# Pure_VCF.net
KiCad netlist of a schematic drawn in EAGLE
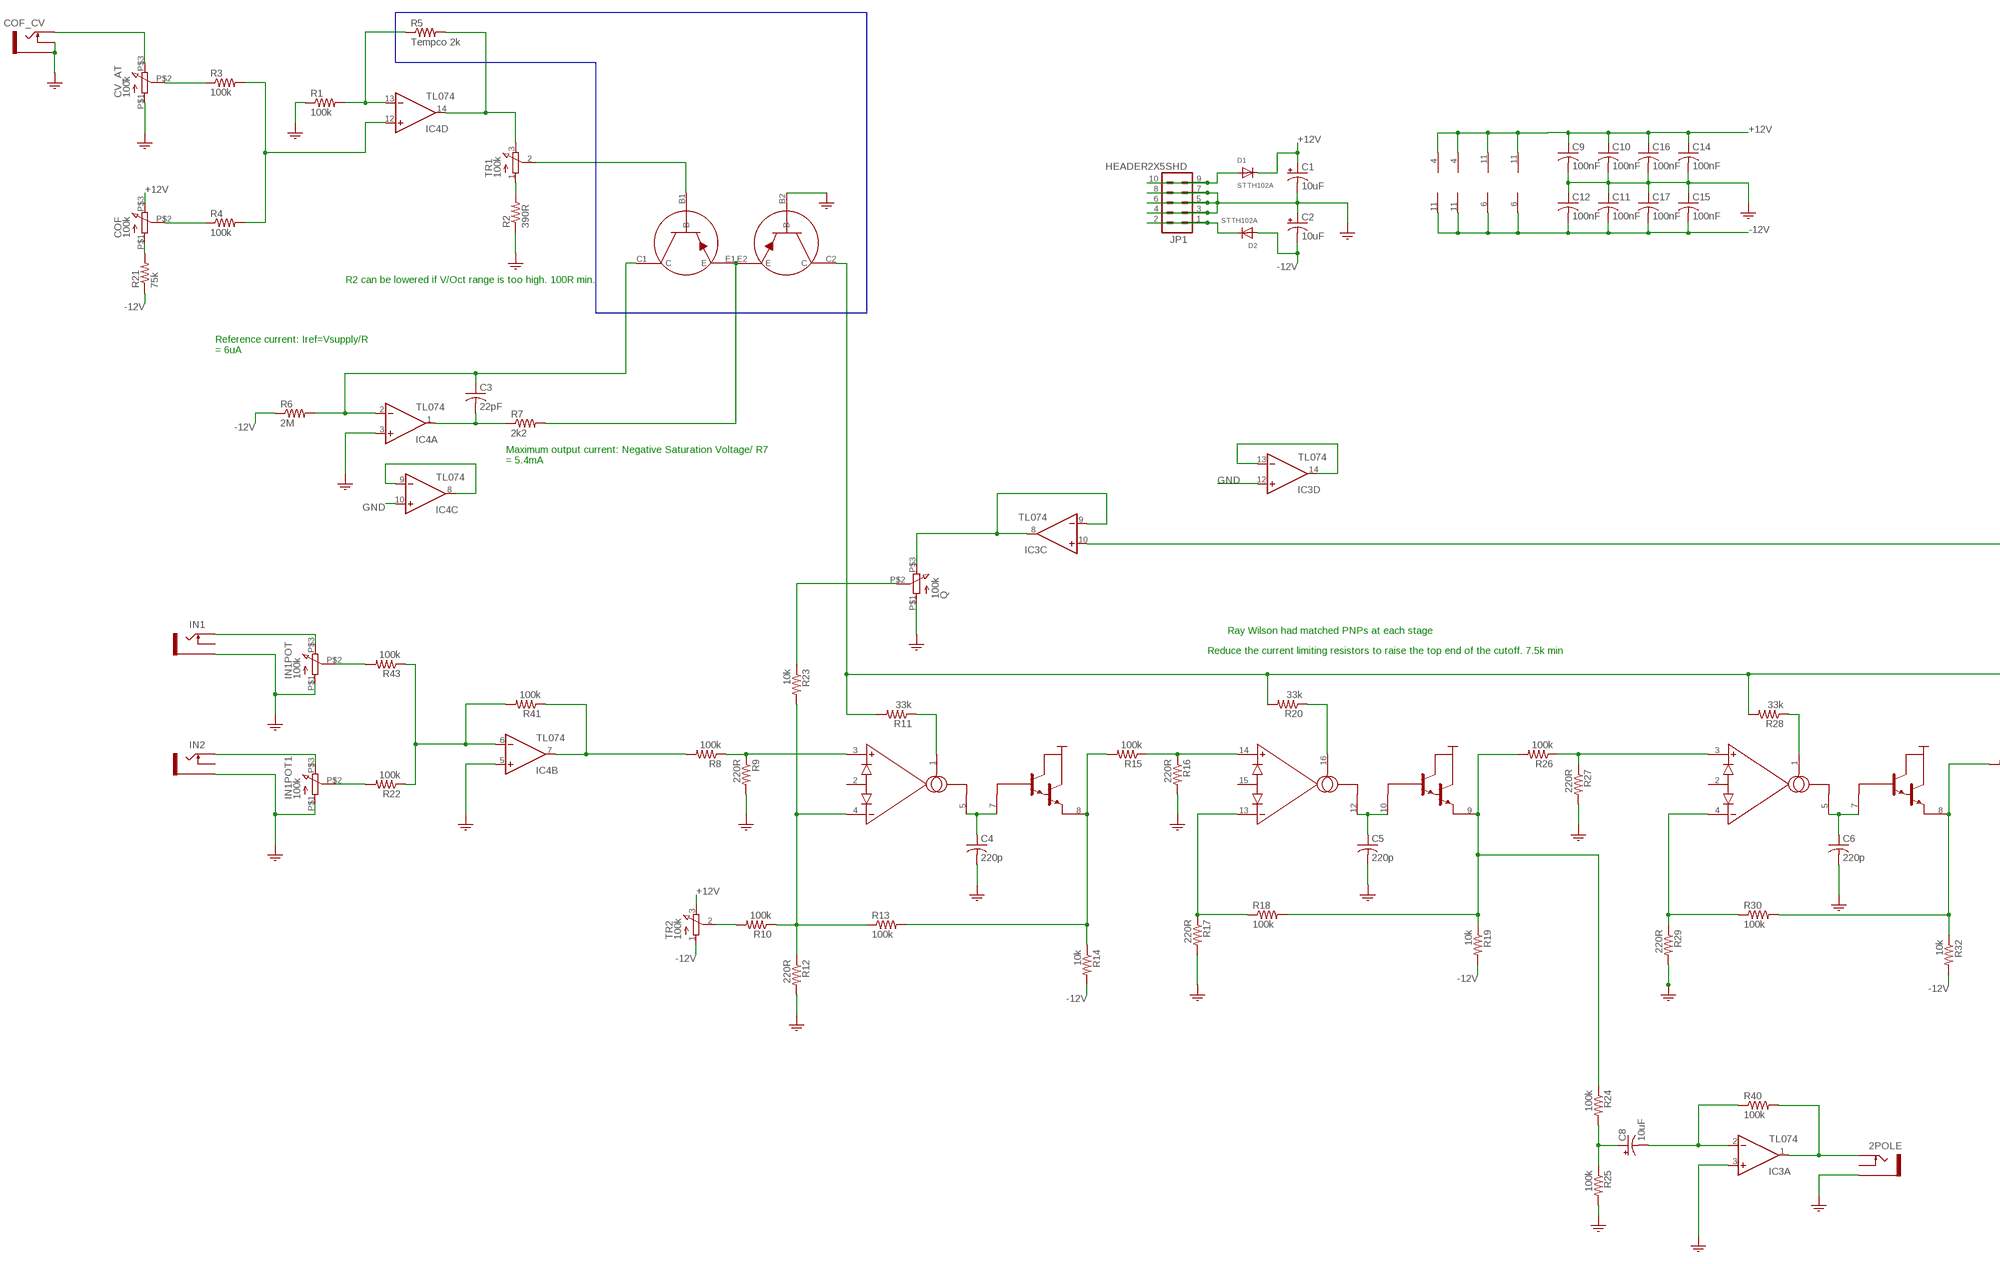
[diagram p0: schematic, sheet 1, part 1 of 2]
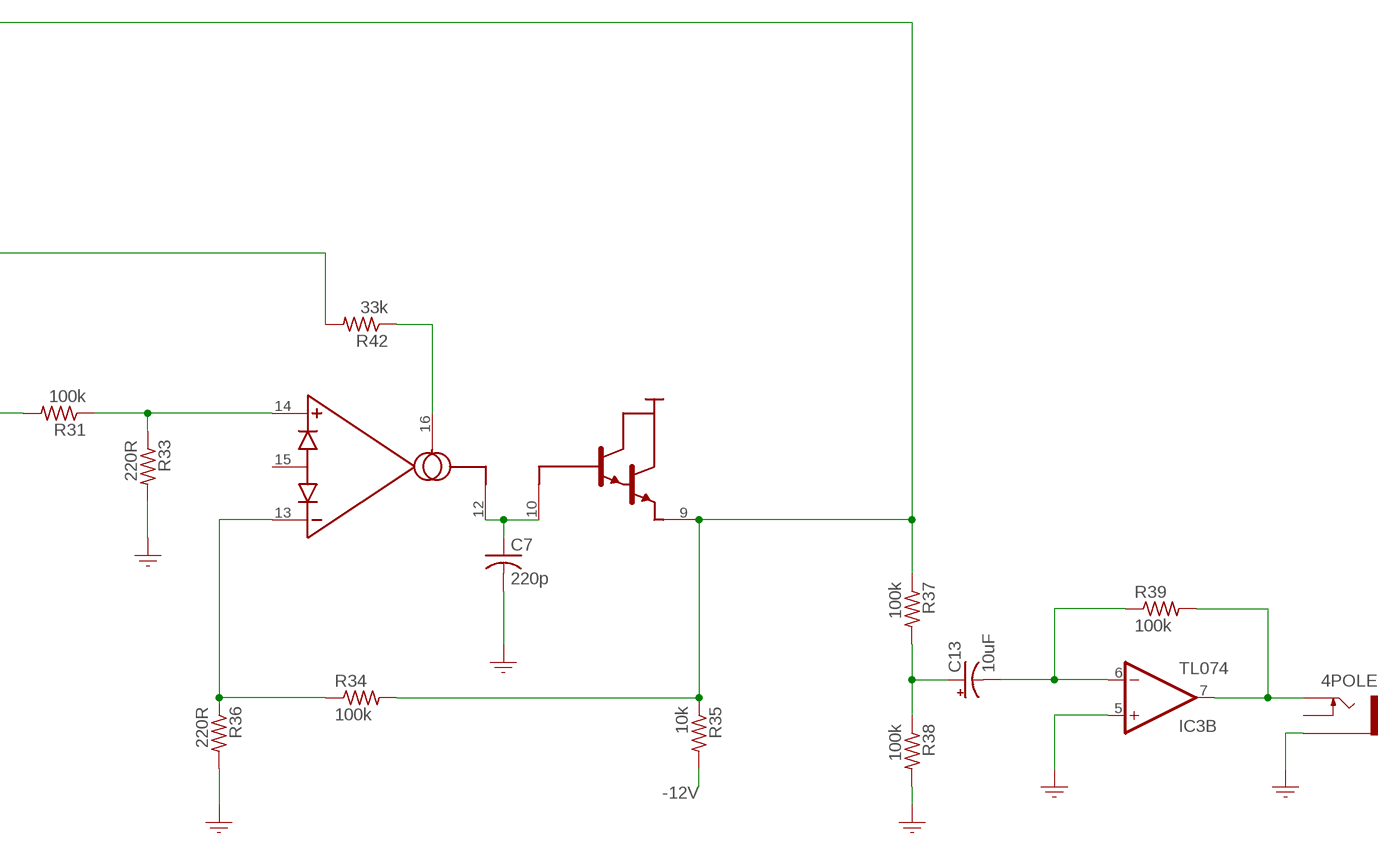
[diagram p1: schematic, sheet 1, part 2 of 2]

(export (version "E")
  (design (tool "Eeschema 10.0.6"))
  (components
    (comp (ref "2POLE")
      (value "PJ301M-12")
      (footprint "eagle-import:PJ301M-12")
      (libsource (lib "eagle-import") (part "SOCKET_MONO_3.5MMPJ301M-12"))
    )
    (comp (ref "4POLE")
      (value "PJ301M-12")
      (footprint "eagle-import:PJ301M-12")
      (libsource (lib "eagle-import") (part "SOCKET_MONO_3.5MMPJ301M-12"))
    )
    (comp (ref "C1")
      (value "10uF")
      (footprint "eagle-import:153CLV-0505")
      (libsource (lib "eagle-import") (part "CAPACITOR_POL-US153CLV-0505"))
    )
    (comp (ref "C2")
      (value "10uF")
      (footprint "eagle-import:153CLV-0505")
      (libsource (lib "eagle-import") (part "CAPACITOR_POL-US153CLV-0505"))
    )
    (comp (ref "C3")
      (value "22pF")
      (footprint "eagle-import:C0805")
      (libsource (lib "eagle-import") (part "CAPACITOR-USC0805"))
    )
    (comp (ref "C4")
      (value "220p")
      (footprint "eagle-import:C050-045X075")
      (libsource (lib "eagle-import") (part "CAPACITOR-US050-045X075"))
    )
    (comp (ref "C5")
      (value "220p")
      (footprint "eagle-import:C050-045X075")
      (libsource (lib "eagle-import") (part "CAPACITOR-US050-045X075"))
    )
    (comp (ref "C6")
      (value "220p")
      (footprint "eagle-import:C050-045X075")
      (libsource (lib "eagle-import") (part "CAPACITOR-US050-045X075"))
    )
    (comp (ref "C7")
      (value "220p")
      (footprint "eagle-import:C050-045X075")
      (libsource (lib "eagle-import") (part "CAPACITOR-US050-045X075"))
    )
    (comp (ref "C8")
      (value "10uF")
      (footprint "eagle-import:153CLV-0505")
      (libsource (lib "eagle-import") (part "CAPACITOR_POL-US153CLV-0505"))
    )
    (comp (ref "C9")
      (value "100nF")
      (footprint "eagle-import:C0805")
      (libsource (lib "eagle-import") (part "CAPACITOR-USC0805"))
    )
    (comp (ref "C10")
      (value "100nF")
      (footprint "eagle-import:C0805")
      (libsource (lib "eagle-import") (part "CAPACITOR-USC0805"))
    )
    (comp (ref "C11")
      (value "100nF")
      (footprint "eagle-import:C0805")
      (libsource (lib "eagle-import") (part "CAPACITOR-USC0805"))
    )
    (comp (ref "C12")
      (value "100nF")
      (footprint "eagle-import:C0805")
      (libsource (lib "eagle-import") (part "CAPACITOR-USC0805"))
    )
    (comp (ref "C13")
      (value "10uF")
      (footprint "eagle-import:153CLV-0505")
      (libsource (lib "eagle-import") (part "CAPACITOR_POL-US153CLV-0505"))
    )
    (comp (ref "C14")
      (value "100nF")
      (footprint "eagle-import:C0805")
      (libsource (lib "eagle-import") (part "CAPACITOR-USC0805"))
    )
    (comp (ref "C15")
      (value "100nF")
      (footprint "eagle-import:C0805")
      (libsource (lib "eagle-import") (part "CAPACITOR-USC0805"))
    )
    (comp (ref "C16")
      (value "100nF")
      (footprint "eagle-import:C0805")
      (libsource (lib "eagle-import") (part "CAPACITOR-USC0805"))
    )
    (comp (ref "C17")
      (value "100nF")
      (footprint "eagle-import:C0805")
      (libsource (lib "eagle-import") (part "CAPACITOR-USC0805"))
    )
    (comp (ref "COF")
      (value "100k")
      (footprint "eagle-import:POTENTIOMETER_9MM")
      (libsource (lib "eagle-import") (part "RESISTOR_VARIABLE9MM_POT"))
    )
    (comp (ref "COF_CV")
      (value "PJ301M-12")
      (footprint "eagle-import:PJ301M-12")
      (libsource (lib "eagle-import") (part "SOCKET_MONO_3.5MMPJ301M-12"))
    )
    (comp (ref "CV_AT")
      (value "100k")
      (footprint "eagle-import:POTENTIOMETER_9MM")
      (libsource (lib "eagle-import") (part "RESISTOR_VARIABLE9MM_POT"))
    )
    (comp (ref "D1")
      (value "STTH102A")
      (footprint "eagle-import:SMADIODE")
      (libsource (lib "eagle-import") (part "DIODESMA"))
    )
    (comp (ref "D2")
      (value "STTH102A")
      (footprint "eagle-import:SMADIODE")
      (libsource (lib "eagle-import") (part "DIODESMA"))
    )
    (comp (ref "IC1")
      (value "LM13700")
      (footprint "eagle-import:SOIC-16_BLANK")
      (libsource (lib "eagle-import") (part "OTA_LM13700"))
    )
    (comp (ref "IC2")
      (value "LM13700")
      (footprint "eagle-import:SOIC-16_BLANK")
      (libsource (lib "eagle-import") (part "OTA_LM13700"))
    )
    (comp (ref "IC3")
      (value "TL074")
      (footprint "eagle-import:SO14")
      (libsource (lib "eagle-import") (part "OPAMP_QUADD"))
    )
    (comp (ref "IC4")
      (value "TL074")
      (footprint "eagle-import:SO14")
      (libsource (lib "eagle-import") (part "OPAMP_QUADD"))
    )
    (comp (ref "IN1")
      (value "PJ301M-12")
      (footprint "eagle-import:PJ301M-12")
      (libsource (lib "eagle-import") (part "SOCKET_MONO_3.5MMPJ301M-12"))
    )
    (comp (ref "IN1POT")
      (value "100k")
      (footprint "eagle-import:POTENTIOMETER_9MM")
      (libsource (lib "eagle-import") (part "RESISTOR_VARIABLE9MM_POT"))
    )
    (comp (ref "IN1POT1")
      (value "100k")
      (footprint "eagle-import:POTENTIOMETER_9MM")
      (libsource (lib "eagle-import") (part "RESISTOR_VARIABLE9MM_POT"))
    )
    (comp (ref "IN2")
      (value "PJ301M-12")
      (footprint "eagle-import:PJ301M-12")
      (libsource (lib "eagle-import") (part "SOCKET_MONO_3.5MMPJ301M-12"))
    )
    (comp (ref "JP1")
      (value "HEADER2X5SHD")
      (footprint "eagle-import:2X5-SHROUDED")
      (libsource (lib "eagle-import") (part "HEADER2X5SHD"))
    )
    (comp (ref "Q")
      (value "100k")
      (footprint "eagle-import:POTENTIOMETER_9MM")
      (libsource (lib "eagle-import") (part "RESISTOR_VARIABLE9MM_POT"))
    )
    (comp (ref "R1")
      (value "100k")
      (footprint "eagle-import:R0805")
      (libsource (lib "eagle-import") (part "RESISTOR_USR0805"))
    )
    (comp (ref "R2")
      (value "390R")
      (footprint "eagle-import:R0805")
      (libsource (lib "eagle-import") (part "RESISTOR_USR0805"))
    )
    (comp (ref "R3")
      (value "100k")
      (footprint "eagle-import:R0805")
      (libsource (lib "eagle-import") (part "RESISTOR_USR0805"))
    )
    (comp (ref "R4")
      (value "100k")
      (footprint "eagle-import:R0805")
      (libsource (lib "eagle-import") (part "RESISTOR_USR0805"))
    )
    (comp (ref "R5")
      (value "Tempco 2k")
      (footprint "eagle-import:0204_7")
      (libsource (lib "eagle-import") (part "RESISTOR_US0204/7"))
    )
    (comp (ref "R6")
      (value "2M")
      (footprint "eagle-import:R0805")
      (libsource (lib "eagle-import") (part "RESISTOR_USR0805"))
    )
    (comp (ref "R7")
      (value "2k2")
      (footprint "eagle-import:R0805")
      (libsource (lib "eagle-import") (part "RESISTOR_USR0805"))
    )
    (comp (ref "R8")
      (value "100k")
      (footprint "eagle-import:R0805")
      (libsource (lib "eagle-import") (part "RESISTOR_USR0805"))
    )
    (comp (ref "R9")
      (value "220R")
      (footprint "eagle-import:R0805")
      (libsource (lib "eagle-import") (part "RESISTOR_USR0805"))
    )
    (comp (ref "R10")
      (value "100k")
      (footprint "eagle-import:R0805")
      (libsource (lib "eagle-import") (part "RESISTOR_USR0805"))
    )
    (comp (ref "R11")
      (value "33k")
      (footprint "eagle-import:R0805")
      (libsource (lib "eagle-import") (part "RESISTOR_USR0805"))
    )
    (comp (ref "R12")
      (value "220R")
      (footprint "eagle-import:R0805")
      (libsource (lib "eagle-import") (part "RESISTOR_USR0805"))
    )
    (comp (ref "R13")
      (value "100k")
      (footprint "eagle-import:R0805")
      (libsource (lib "eagle-import") (part "RESISTOR_USR0805"))
    )
    (comp (ref "R14")
      (value "10k")
      (footprint "eagle-import:R0805")
      (libsource (lib "eagle-import") (part "RESISTOR_USR0805"))
    )
    (comp (ref "R15")
      (value "100k")
      (footprint "eagle-import:R0805")
      (libsource (lib "eagle-import") (part "RESISTOR_USR0805"))
    )
    (comp (ref "R16")
      (value "220R")
      (footprint "eagle-import:R0805")
      (libsource (lib "eagle-import") (part "RESISTOR_USR0805"))
    )
    (comp (ref "R17")
      (value "220R")
      (footprint "eagle-import:R0805")
      (libsource (lib "eagle-import") (part "RESISTOR_USR0805"))
    )
    (comp (ref "R18")
      (value "100k")
      (footprint "eagle-import:R0805")
      (libsource (lib "eagle-import") (part "RESISTOR_USR0805"))
    )
    (comp (ref "R19")
      (value "10k")
      (footprint "eagle-import:R0805")
      (libsource (lib "eagle-import") (part "RESISTOR_USR0805"))
    )
    (comp (ref "R20")
      (value "33k")
      (footprint "eagle-import:R0805")
      (libsource (lib "eagle-import") (part "RESISTOR_USR0805"))
    )
    (comp (ref "R21")
      (value "75k")
      (footprint "eagle-import:R0805")
      (libsource (lib "eagle-import") (part "RESISTOR_USR0805"))
    )
    (comp (ref "R22")
      (value "100k")
      (footprint "eagle-import:R0805")
      (libsource (lib "eagle-import") (part "RESISTOR_USR0805"))
    )
    (comp (ref "R23")
      (value "10k")
      (footprint "eagle-import:R0805")
      (libsource (lib "eagle-import") (part "RESISTOR_USR0805"))
    )
    (comp (ref "R24")
      (value "100k")
      (footprint "eagle-import:R0805")
      (libsource (lib "eagle-import") (part "RESISTOR_USR0805"))
    )
    (comp (ref "R25")
      (value "100k")
      (footprint "eagle-import:R0805")
      (libsource (lib "eagle-import") (part "RESISTOR_USR0805"))
    )
    (comp (ref "R26")
      (value "100k")
      (footprint "eagle-import:R0805")
      (libsource (lib "eagle-import") (part "RESISTOR_USR0805"))
    )
    (comp (ref "R27")
      (value "220R")
      (footprint "eagle-import:R0805")
      (libsource (lib "eagle-import") (part "RESISTOR_USR0805"))
    )
    (comp (ref "R28")
      (value "33k")
      (footprint "eagle-import:R0805")
      (libsource (lib "eagle-import") (part "RESISTOR_USR0805"))
    )
    (comp (ref "R29")
      (value "220R")
      (footprint "eagle-import:R0805")
      (libsource (lib "eagle-import") (part "RESISTOR_USR0805"))
    )
    (comp (ref "R30")
      (value "100k")
      (footprint "eagle-import:R0805")
      (libsource (lib "eagle-import") (part "RESISTOR_USR0805"))
    )
    (comp (ref "R31")
      (value "100k")
      (footprint "eagle-import:R0805")
      (libsource (lib "eagle-import") (part "RESISTOR_USR0805"))
    )
    (comp (ref "R32")
      (value "10k")
      (footprint "eagle-import:R0805")
      (libsource (lib "eagle-import") (part "RESISTOR_USR0805"))
    )
    (comp (ref "R33")
      (value "220R")
      (footprint "eagle-import:R0805")
      (libsource (lib "eagle-import") (part "RESISTOR_USR0805"))
    )
    (comp (ref "R34")
      (value "100k")
      (footprint "eagle-import:R0805")
      (libsource (lib "eagle-import") (part "RESISTOR_USR0805"))
    )
    (comp (ref "R35")
      (value "10k")
      (footprint "eagle-import:R0805")
      (libsource (lib "eagle-import") (part "RESISTOR_USR0805"))
    )
    (comp (ref "R36")
      (value "220R")
      (footprint "eagle-import:R0805")
      (libsource (lib "eagle-import") (part "RESISTOR_USR0805"))
    )
    (comp (ref "R37")
      (value "100k")
      (footprint "eagle-import:R0805")
      (libsource (lib "eagle-import") (part "RESISTOR_USR0805"))
    )
    (comp (ref "R38")
      (value "100k")
      (footprint "eagle-import:R0805")
      (libsource (lib "eagle-import") (part "RESISTOR_USR0805"))
    )
    (comp (ref "R39")
      (value "100k")
      (footprint "eagle-import:R0805")
      (libsource (lib "eagle-import") (part "RESISTOR_USR0805"))
    )
    (comp (ref "R40")
      (value "100k")
      (footprint "eagle-import:R0805")
      (libsource (lib "eagle-import") (part "RESISTOR_USR0805"))
    )
    (comp (ref "R41")
      (value "100k")
      (footprint "eagle-import:R0805")
      (libsource (lib "eagle-import") (part "RESISTOR_USR0805"))
    )
    (comp (ref "R42")
      (value "33k")
      (footprint "eagle-import:R0805")
      (libsource (lib "eagle-import") (part "RESISTOR_USR0805"))
    )
    (comp (ref "R43")
      (value "100k")
      (footprint "eagle-import:R0805")
      (libsource (lib "eagle-import") (part "RESISTOR_USR0805"))
    )
    (comp (ref "T1")
      (value "DMMT3906W")
      (footprint "eagle-import:TRANS_PAIR")
      (libsource (lib "eagle-import") (part "TRANSISTOR_PAIR_PNP"))
    )
    (comp (ref "TR1")
      (value "100k")
      (footprint "eagle-import:TRIMMER_TH")
      (libsource (lib "eagle-import") (part "RESISTOR_VARIABLETRIMMER_TH"))
    )
    (comp (ref "TR2")
      (value "100k")
      (footprint "eagle-import:TRIMMER_TH")
      (libsource (lib "eagle-import") (part "RESISTOR_VARIABLETRIMMER_TH"))
    )
  )
  (nets
    (net (code "1") (name "/+12V") (class "Default")
      (node (ref "C1") (pin "+") (pinfunction "+_+") (pintype "passive"))
      (node (ref "C10") (pin "1") (pinfunction "1_1") (pintype "passive"))
      (node (ref "C14") (pin "1") (pinfunction "1_1") (pintype "passive"))
      (node (ref "C16") (pin "1") (pinfunction "1_1") (pintype "passive"))
      (node (ref "C9") (pin "1") (pinfunction "1_1") (pintype "passive"))
      (node (ref "COF") (pin "P$3") (pinfunction "3_P$3") (pintype "passive"))
      (node (ref "D1") (pin "C") (pinfunction "C_C") (pintype "passive"))
      (node (ref "IC1") (pin "11") (pinfunction "V+_11") (pintype "power_in"))
      (node (ref "IC2") (pin "11") (pinfunction "V+_11") (pintype "power_in"))
      (node (ref "IC3") (pin "4") (pinfunction "V+_4") (pintype "power_in"))
      (node (ref "IC4") (pin "4") (pinfunction "V+_4") (pintype "power_in"))
      (node (ref "TR2") (pin "3") (pinfunction "3_3") (pintype "passive"))
    )
    (net (code "2") (name "/-12V") (class "Default")
      (node (ref "C11") (pin "2") (pinfunction "2_2") (pintype "passive"))
      (node (ref "C12") (pin "2") (pinfunction "2_2") (pintype "passive"))
      (node (ref "C15") (pin "2") (pinfunction "2_2") (pintype "passive"))
      (node (ref "C17") (pin "2") (pinfunction "2_2") (pintype "passive"))
      (node (ref "C2") (pin "-") (pinfunction "-_-") (pintype "passive"))
      (node (ref "D2") (pin "A") (pinfunction "A_A") (pintype "passive"))
      (node (ref "IC1") (pin "6") (pinfunction "V-_6") (pintype "power_in"))
      (node (ref "IC2") (pin "6") (pinfunction "V-_6") (pintype "power_in"))
      (node (ref "IC3") (pin "11") (pinfunction "V-_11") (pintype "power_in"))
      (node (ref "IC4") (pin "11") (pinfunction "V-_11") (pintype "power_in"))
      (node (ref "R14") (pin "2") (pinfunction "2_2") (pintype "passive"))
      (node (ref "R19") (pin "2") (pinfunction "2_2") (pintype "passive"))
      (node (ref "R21") (pin "1") (pinfunction "1_1") (pintype "passive"))
      (node (ref "R32") (pin "2") (pinfunction "2_2") (pintype "passive"))
      (node (ref "R35") (pin "2") (pinfunction "2_2") (pintype "passive"))
      (node (ref "R6") (pin "1") (pinfunction "1_1") (pintype "passive"))
      (node (ref "TR2") (pin "1") (pinfunction "1_1") (pintype "passive"))
    )
    (net (code "3") (name "GND") (class "Default")
      (node (ref "2POLE") (pin "GND") (pinfunction "SLEEVE_GND") (pintype "passive"))
      (node (ref "4POLE") (pin "GND") (pinfunction "SLEEVE_GND") (pintype "passive"))
      (node (ref "C1") (pin "-") (pinfunction "-_-") (pintype "passive"))
      (node (ref "C10") (pin "2") (pinfunction "2_2") (pintype "passive"))
      (node (ref "C11") (pin "1") (pinfunction "1_1") (pintype "passive"))
      (node (ref "C12") (pin "1") (pinfunction "1_1") (pintype "passive"))
      (node (ref "C14") (pin "2") (pinfunction "2_2") (pintype "passive"))
      (node (ref "C15") (pin "1") (pinfunction "1_1") (pintype "passive"))
      (node (ref "C16") (pin "2") (pinfunction "2_2") (pintype "passive"))
      (node (ref "C17") (pin "1") (pinfunction "1_1") (pintype "passive"))
      (node (ref "C2") (pin "+") (pinfunction "+_+") (pintype "passive"))
      (node (ref "C4") (pin "2") (pinfunction "2_2") (pintype "passive"))
      (node (ref "C5") (pin "2") (pinfunction "2_2") (pintype "passive"))
      (node (ref "C6") (pin "2") (pinfunction "2_2") (pintype "passive"))
      (node (ref "C7") (pin "2") (pinfunction "2_2") (pintype "passive"))
      (node (ref "C9") (pin "2") (pinfunction "2_2") (pintype "passive"))
      (node (ref "COF_CV") (pin "GND") (pinfunction "SLEEVE_GND") (pintype "passive"))
      (node (ref "COF_CV") (pin "NORM") (pinfunction "SWITCH_NORM") (pintype "passive"))
      (node (ref "CV_AT") (pin "P$1") (pinfunction "1_P$1") (pintype "passive"))
      (node (ref "IC3") (pin "12") (pinfunction "+IN_12") (pintype "input"))
      (node (ref "IC3") (pin "3") (pinfunction "+IN_3") (pintype "input"))
      (node (ref "IC3") (pin "5") (pinfunction "+IN_5") (pintype "input"))
      (node (ref "IC4") (pin "10") (pinfunction "+IN_10") (pintype "input"))
      (node (ref "IC4") (pin "3") (pinfunction "+IN_3") (pintype "input"))
      (node (ref "IC4") (pin "5") (pinfunction "+IN_5") (pintype "input"))
      (node (ref "IN1") (pin "GND") (pinfunction "SLEEVE_GND") (pintype "passive"))
      (node (ref "IN1POT") (pin "P$1") (pinfunction "1_P$1") (pintype "passive"))
      (node (ref "IN1POT1") (pin "P$1") (pinfunction "1_P$1") (pintype "passive"))
      (node (ref "IN2") (pin "GND") (pinfunction "SLEEVE_GND") (pintype "passive"))
      (node (ref "JP1") (pin "3") (pinfunction "3_3") (pintype "passive"))
      (node (ref "JP1") (pin "4") (pinfunction "4_4") (pintype "passive"))
      (node (ref "JP1") (pin "5") (pinfunction "5_5") (pintype "passive"))
      (node (ref "JP1") (pin "6") (pinfunction "6_6") (pintype "passive"))
      (node (ref "JP1") (pin "7") (pinfunction "7_7") (pintype "passive"))
      (node (ref "JP1") (pin "8") (pinfunction "8_8") (pintype "passive"))
      (node (ref "Q") (pin "P$1") (pinfunction "1_P$1") (pintype "passive"))
      (node (ref "R1") (pin "1") (pinfunction "1_1") (pintype "passive"))
      (node (ref "R12") (pin "2") (pinfunction "2_2") (pintype "passive"))
      (node (ref "R16") (pin "2") (pinfunction "2_2") (pintype "passive"))
      (node (ref "R17") (pin "2") (pinfunction "2_2") (pintype "passive"))
      (node (ref "R2") (pin "1") (pinfunction "1_1") (pintype "passive"))
      (node (ref "R25") (pin "2") (pinfunction "2_2") (pintype "passive"))
      (node (ref "R27") (pin "2") (pinfunction "2_2") (pintype "passive"))
      (node (ref "R29") (pin "2") (pinfunction "2_2") (pintype "passive"))
      (node (ref "R33") (pin "2") (pinfunction "2_2") (pintype "passive"))
      (node (ref "R36") (pin "2") (pinfunction "2_2") (pintype "passive"))
      (node (ref "R38") (pin "2") (pinfunction "2_2") (pintype "passive"))
      (node (ref "R9") (pin "2") (pinfunction "2_2") (pintype "passive"))
      (node (ref "T1") (pin "B2") (pinfunction "B_B2") (pintype "bidirectional"))
    )
    (net (code "4") (name "Net-(C8-Pad+)") (class "Default")
      (node (ref "C8") (pin "+") (pinfunction "+_+") (pintype "passive"))
      (node (ref "R24") (pin "2") (pinfunction "2_2") (pintype "passive"))
      (node (ref "R25") (pin "1") (pinfunction "1_1") (pintype "passive"))
    )
    (net (code "5") (name "Net-(C13-Pad+)") (class "Default")
      (node (ref "C13") (pin "+") (pinfunction "+_+") (pintype "passive"))
      (node (ref "R37") (pin "2") (pinfunction "2_2") (pintype "passive"))
      (node (ref "R38") (pin "1") (pinfunction "1_1") (pintype "passive"))
    )
    (net (code "6") (name "Net-(COF-1)") (class "Default")
      (node (ref "COF") (pin "P$1") (pinfunction "1_P$1") (pintype "passive"))
      (node (ref "R21") (pin "2") (pinfunction "2_2") (pintype "passive"))
    )
    (net (code "7") (name "Net-(COF-2)") (class "Default")
      (node (ref "COF") (pin "P$2") (pinfunction "2_P$2") (pintype "passive"))
      (node (ref "R4") (pin "1") (pinfunction "1_1") (pintype "passive"))
    )
    (net (code "8") (name "Net-(CV_AT-2)") (class "Default")
      (node (ref "CV_AT") (pin "P$2") (pinfunction "2_P$2") (pintype "passive"))
      (node (ref "R3") (pin "1") (pinfunction "1_1") (pintype "passive"))
    )
    (net (code "9") (name "Net-(CV_AT-3)") (class "Default")
      (node (ref "COF_CV") (pin "TIP") (pinfunction "TIP_TIP") (pintype "passive"))
      (node (ref "CV_AT") (pin "P$3") (pinfunction "3_P$3") (pintype "passive"))
    )
    (net (code "10") (name "Net-(D1-PadA)") (class "Default")
      (node (ref "D1") (pin "A") (pinfunction "A_A") (pintype "passive"))
      (node (ref "JP1") (pin "10") (pinfunction "10_10") (pintype "passive"))
      (node (ref "JP1") (pin "9") (pinfunction "9_9") (pintype "passive"))
    )
    (net (code "11") (name "Net-(D2-PadC)") (class "Default")
      (node (ref "D2") (pin "C") (pinfunction "C_C") (pintype "passive"))
      (node (ref "JP1") (pin "1") (pinfunction "1_1") (pintype "passive"))
      (node (ref "JP1") (pin "2") (pinfunction "2_2") (pintype "passive"))
    )
    (net (code "12") (name "Net-(IC1A-BIAS-IN)") (class "Default")
      (node (ref "IC1") (pin "1") (pinfunction "BIAS-IN_1") (pintype "bidirectional"))
      (node (ref "R11") (pin "1") (pinfunction "1_1") (pintype "passive"))
    )
    (net (code "13") (name "Net-(IC1A-BUF-IN_2)") (class "Default")
      (node (ref "C4") (pin "1") (pinfunction "1_1") (pintype "passive"))
      (node (ref "IC1") (pin "5") (pinfunction "OUT_5") (pintype "bidirectional"))
      (node (ref "IC1") (pin "7") (pinfunction "BUF-IN_2_7") (pintype "bidirectional"))
    )
    (net (code "14") (name "Net-(IC1A-BUF-OUT_2)") (class "Default")
      (node (ref "IC1") (pin "8") (pinfunction "BUF-OUT_2_8") (pintype "bidirectional"))
      (node (ref "R13") (pin "2") (pinfunction "2_2") (pintype "passive"))
      (node (ref "R14") (pin "1") (pinfunction "1_1") (pintype "passive"))
      (node (ref "R15") (pin "2") (pinfunction "2_2") (pintype "passive"))
    )
    (net (code "15") (name "Net-(IC1A-IN+)") (class "Default")
      (node (ref "IC1") (pin "3") (pinfunction "IN+_3") (pintype "bidirectional"))
      (node (ref "R8") (pin "1") (pinfunction "1_1") (pintype "passive"))
      (node (ref "R9") (pin "1") (pinfunction "1_1") (pintype "passive"))
    )
    (net (code "16") (name "Net-(IC1A-IN-)") (class "Default")
      (node (ref "IC1") (pin "4") (pinfunction "IN-_4") (pintype "bidirectional"))
      (node (ref "R10") (pin "1") (pinfunction "1_1") (pintype "passive"))
      (node (ref "R12") (pin "1") (pinfunction "1_1") (pintype "passive"))
      (node (ref "R13") (pin "1") (pinfunction "1_1") (pintype "passive"))
      (node (ref "R23") (pin "2") (pinfunction "2_2") (pintype "passive"))
    )
    (net (code "17") (name "Net-(IC1B-BIAS-IN)") (class "Default")
      (node (ref "IC1") (pin "16") (pinfunction "BIAS-IN_16") (pintype "bidirectional"))
      (node (ref "R20") (pin "1") (pinfunction "1_1") (pintype "passive"))
    )
    (net (code "18") (name "Net-(IC1B-BUF-IN_2)") (class "Default")
      (node (ref "C5") (pin "1") (pinfunction "1_1") (pintype "passive"))
      (node (ref "IC1") (pin "10") (pinfunction "BUF-IN_2_10") (pintype "bidirectional"))
      (node (ref "IC1") (pin "12") (pinfunction "OUT_12") (pintype "bidirectional"))
    )
    (net (code "19") (name "Net-(IC1B-BUF-OUT_2)") (class "Default")
      (node (ref "IC1") (pin "9") (pinfunction "BUF-OUT_2_9") (pintype "bidirectional"))
      (node (ref "R18") (pin "2") (pinfunction "2_2") (pintype "passive"))
      (node (ref "R19") (pin "1") (pinfunction "1_1") (pintype "passive"))
      (node (ref "R24") (pin "1") (pinfunction "1_1") (pintype "passive"))
      (node (ref "R26") (pin "2") (pinfunction "2_2") (pintype "passive"))
    )
    (net (code "20") (name "Net-(IC1B-IN+)") (class "Default")
      (node (ref "IC1") (pin "14") (pinfunction "IN+_14") (pintype "bidirectional"))
      (node (ref "R15") (pin "1") (pinfunction "1_1") (pintype "passive"))
      (node (ref "R16") (pin "1") (pinfunction "1_1") (pintype "passive"))
    )
    (net (code "21") (name "Net-(IC1B-IN-)") (class "Default")
      (node (ref "IC1") (pin "13") (pinfunction "IN-_13") (pintype "bidirectional"))
      (node (ref "R17") (pin "1") (pinfunction "1_1") (pintype "passive"))
      (node (ref "R18") (pin "1") (pinfunction "1_1") (pintype "passive"))
    )
    (net (code "22") (name "Net-(IC2A-BIAS-IN)") (class "Default")
      (node (ref "IC2") (pin "1") (pinfunction "BIAS-IN_1") (pintype "bidirectional"))
      (node (ref "R28") (pin "1") (pinfunction "1_1") (pintype "passive"))
    )
    (net (code "23") (name "Net-(IC2A-BUF-IN_2)") (class "Default")
      (node (ref "C6") (pin "1") (pinfunction "1_1") (pintype "passive"))
      (node (ref "IC2") (pin "5") (pinfunction "OUT_5") (pintype "bidirectional"))
      (node (ref "IC2") (pin "7") (pinfunction "BUF-IN_2_7") (pintype "bidirectional"))
    )
    (net (code "24") (name "Net-(IC2A-BUF-OUT_2)") (class "Default")
      (node (ref "IC2") (pin "8") (pinfunction "BUF-OUT_2_8") (pintype "bidirectional"))
      (node (ref "R30") (pin "2") (pinfunction "2_2") (pintype "passive"))
      (node (ref "R31") (pin "2") (pinfunction "2_2") (pintype "passive"))
      (node (ref "R32") (pin "1") (pinfunction "1_1") (pintype "passive"))
    )
    (net (code "25") (name "Net-(IC2A-IN+)") (class "Default")
      (node (ref "IC2") (pin "3") (pinfunction "IN+_3") (pintype "bidirectional"))
      (node (ref "R26") (pin "1") (pinfunction "1_1") (pintype "passive"))
      (node (ref "R27") (pin "1") (pinfunction "1_1") (pintype "passive"))
    )
    (net (code "26") (name "Net-(IC2A-IN-)") (class "Default")
      (node (ref "IC2") (pin "4") (pinfunction "IN-_4") (pintype "bidirectional"))
      (node (ref "R29") (pin "1") (pinfunction "1_1") (pintype "passive"))
      (node (ref "R30") (pin "1") (pinfunction "1_1") (pintype "passive"))
    )
    (net (code "27") (name "Net-(IC2B-BIAS-IN)") (class "Default")
      (node (ref "IC2") (pin "16") (pinfunction "BIAS-IN_16") (pintype "bidirectional"))
      (node (ref "R42") (pin "1") (pinfunction "1_1") (pintype "passive"))
    )
    (net (code "28") (name "Net-(IC2B-BUF-IN_2)") (class "Default")
      (node (ref "C7") (pin "1") (pinfunction "1_1") (pintype "passive"))
      (node (ref "IC2") (pin "10") (pinfunction "BUF-IN_2_10") (pintype "bidirectional"))
      (node (ref "IC2") (pin "12") (pinfunction "OUT_12") (pintype "bidirectional"))
    )
    (net (code "29") (name "Net-(IC2B-BUF-OUT_2)") (class "Default")
      (node (ref "IC2") (pin "9") (pinfunction "BUF-OUT_2_9") (pintype "bidirectional"))
      (node (ref "IC3") (pin "10") (pinfunction "+IN_10") (pintype "input"))
      (node (ref "R34") (pin "2") (pinfunction "2_2") (pintype "passive"))
      (node (ref "R35") (pin "1") (pinfunction "1_1") (pintype "passive"))
      (node (ref "R37") (pin "1") (pinfunction "1_1") (pintype "passive"))
    )
    (net (code "30") (name "Net-(IC2B-IN+)") (class "Default")
      (node (ref "IC2") (pin "14") (pinfunction "IN+_14") (pintype "bidirectional"))
      (node (ref "R31") (pin "1") (pinfunction "1_1") (pintype "passive"))
      (node (ref "R33") (pin "1") (pinfunction "1_1") (pintype "passive"))
    )
    (net (code "31") (name "Net-(IC2B-IN-)") (class "Default")
      (node (ref "IC2") (pin "13") (pinfunction "IN-_13") (pintype "bidirectional"))
      (node (ref "R34") (pin "1") (pinfunction "1_1") (pintype "passive"))
      (node (ref "R36") (pin "1") (pinfunction "1_1") (pintype "passive"))
    )
    (net (code "32") (name "Net-(IC3A--IN)") (class "Default")
      (node (ref "C8") (pin "-") (pinfunction "-_-") (pintype "passive"))
      (node (ref "IC3") (pin "2") (pinfunction "-IN_2") (pintype "input"))
      (node (ref "R40") (pin "1") (pinfunction "1_1") (pintype "passive"))
    )
    (net (code "33") (name "Net-(IC3A-OUT)") (class "Default")
      (node (ref "2POLE") (pin "TIP") (pinfunction "TIP_TIP") (pintype "passive"))
      (node (ref "IC3") (pin "1") (pinfunction "OUT_1") (pintype "output"))
      (node (ref "R40") (pin "2") (pinfunction "2_2") (pintype "passive"))
    )
    (net (code "34") (name "Net-(IC3B--IN)") (class "Default")
      (node (ref "C13") (pin "-") (pinfunction "-_-") (pintype "passive"))
      (node (ref "IC3") (pin "6") (pinfunction "-IN_6") (pintype "input"))
      (node (ref "R39") (pin "1") (pinfunction "1_1") (pintype "passive"))
    )
    (net (code "35") (name "Net-(IC3B-OUT)") (class "Default")
      (node (ref "4POLE") (pin "TIP") (pinfunction "TIP_TIP") (pintype "passive"))
      (node (ref "IC3") (pin "7") (pinfunction "OUT_7") (pintype "output"))
      (node (ref "R39") (pin "2") (pinfunction "2_2") (pintype "passive"))
    )
    (net (code "36") (name "Net-(IC3C--IN)") (class "Default")
      (node (ref "IC3") (pin "8") (pinfunction "OUT_8") (pintype "output"))
      (node (ref "IC3") (pin "9") (pinfunction "-IN_9") (pintype "input"))
      (node (ref "Q") (pin "P$3") (pinfunction "3_P$3") (pintype "passive"))
    )
    (net (code "37") (name "Net-(IC3D--IN)") (class "Default")
      (node (ref "IC3") (pin "13") (pinfunction "-IN_13") (pintype "input"))
      (node (ref "IC3") (pin "14") (pinfunction "OUT_14") (pintype "output"))
    )
    (net (code "38") (name "Net-(IC4A--IN)") (class "Default")
      (node (ref "C3") (pin "1") (pinfunction "1_1") (pintype "passive"))
      (node (ref "IC4") (pin "2") (pinfunction "-IN_2") (pintype "input"))
      (node (ref "R6") (pin "2") (pinfunction "2_2") (pintype "passive"))
      (node (ref "T1") (pin "C1") (pinfunction "C_C1") (pintype "bidirectional"))
    )
    (net (code "39") (name "Net-(IC4A-OUT)") (class "Default")
      (node (ref "C3") (pin "2") (pinfunction "2_2") (pintype "passive"))
      (node (ref "IC4") (pin "1") (pinfunction "OUT_1") (pintype "output"))
      (node (ref "R7") (pin "1") (pinfunction "1_1") (pintype "passive"))
    )
    (net (code "40") (name "Net-(IC4B--IN)") (class "Default")
      (node (ref "IC4") (pin "6") (pinfunction "-IN_6") (pintype "input"))
      (node (ref "R22") (pin "1") (pinfunction "1_1") (pintype "passive"))
      (node (ref "R41") (pin "2") (pinfunction "2_2") (pintype "passive"))
      (node (ref "R43") (pin "1") (pinfunction "1_1") (pintype "passive"))
    )
    (net (code "41") (name "Net-(IC4B-OUT)") (class "Default")
      (node (ref "IC4") (pin "7") (pinfunction "OUT_7") (pintype "output"))
      (node (ref "R41") (pin "1") (pinfunction "1_1") (pintype "passive"))
      (node (ref "R8") (pin "2") (pinfunction "2_2") (pintype "passive"))
    )
    (net (code "42") (name "Net-(IC4C--IN)") (class "Default")
      (node (ref "IC4") (pin "8") (pinfunction "OUT_8") (pintype "output"))
      (node (ref "IC4") (pin "9") (pinfunction "-IN_9") (pintype "input"))
    )
    (net (code "43") (name "Net-(IC4D-+IN)") (class "Default")
      (node (ref "IC4") (pin "12") (pinfunction "+IN_12") (pintype "input"))
      (node (ref "R3") (pin "2") (pinfunction "2_2") (pintype "passive"))
      (node (ref "R4") (pin "2") (pinfunction "2_2") (pintype "passive"))
    )
    (net (code "44") (name "Net-(IC4D--IN)") (class "Default")
      (node (ref "IC4") (pin "13") (pinfunction "-IN_13") (pintype "input"))
      (node (ref "R1") (pin "2") (pinfunction "2_2") (pintype "passive"))
      (node (ref "R5") (pin "1") (pinfunction "1_1") (pintype "passive"))
    )
    (net (code "45") (name "Net-(IC4D-OUT)") (class "Default")
      (node (ref "IC4") (pin "14") (pinfunction "OUT_14") (pintype "output"))
      (node (ref "R5") (pin "2") (pinfunction "2_2") (pintype "passive"))
      (node (ref "TR1") (pin "3") (pinfunction "3_3") (pintype "passive"))
    )
    (net (code "46") (name "Net-(IN1POT-2)") (class "Default")
      (node (ref "IN1POT") (pin "P$2") (pinfunction "2_P$2") (pintype "passive"))
      (node (ref "R43") (pin "2") (pinfunction "2_2") (pintype "passive"))
    )
    (net (code "47") (name "Net-(IN1POT-3)") (class "Default")
      (node (ref "IN1") (pin "TIP") (pinfunction "TIP_TIP") (pintype "passive"))
      (node (ref "IN1POT") (pin "P$3") (pinfunction "3_P$3") (pintype "passive"))
    )
    (net (code "48") (name "Net-(IN1POT1-2)") (class "Default")
      (node (ref "IN1POT1") (pin "P$2") (pinfunction "2_P$2") (pintype "passive"))
      (node (ref "R22") (pin "2") (pinfunction "2_2") (pintype "passive"))
    )
    (net (code "49") (name "Net-(IN1POT1-3)") (class "Default")
      (node (ref "IN1POT1") (pin "P$3") (pinfunction "3_P$3") (pintype "passive"))
      (node (ref "IN2") (pin "TIP") (pinfunction "TIP_TIP") (pintype "passive"))
    )
    (net (code "50") (name "Net-(Q-2)") (class "Default")
      (node (ref "Q") (pin "P$2") (pinfunction "2_P$2") (pintype "passive"))
      (node (ref "R23") (pin "1") (pinfunction "1_1") (pintype "passive"))
    )
    (net (code "51") (name "Net-(R2-Pad2)") (class "Default")
      (node (ref "R2") (pin "2") (pinfunction "2_2") (pintype "passive"))
      (node (ref "TR1") (pin "1") (pinfunction "1_1") (pintype "passive"))
    )
    (net (code "52") (name "Net-(R10-Pad2)") (class "Default")
      (node (ref "R10") (pin "2") (pinfunction "2_2") (pintype "passive"))
      (node (ref "TR2") (pin "2") (pinfunction "2_2") (pintype "passive"))
    )
    (net (code "53") (name "Net-(T1A-B)") (class "Default")
      (node (ref "T1") (pin "B1") (pinfunction "B_B1") (pintype "bidirectional"))
      (node (ref "TR1") (pin "2") (pinfunction "2_2") (pintype "passive"))
    )
    (net (code "54") (name "Net-(T1A-E)") (class "Default")
      (node (ref "R7") (pin "2") (pinfunction "2_2") (pintype "passive"))
      (node (ref "T1") (pin "E1") (pinfunction "E_E1") (pintype "bidirectional"))
      (node (ref "T1") (pin "E2") (pinfunction "E_E2") (pintype "bidirectional"))
    )
    (net (code "55") (name "Net-(T1B-C)") (class "Default")
      (node (ref "R11") (pin "2") (pinfunction "2_2") (pintype "passive"))
      (node (ref "R20") (pin "2") (pinfunction "2_2") (pintype "passive"))
      (node (ref "R28") (pin "2") (pinfunction "2_2") (pintype "passive"))
      (node (ref "R42") (pin "2") (pinfunction "2_2") (pintype "passive"))
      (node (ref "T1") (pin "C2") (pinfunction "C_C2") (pintype "bidirectional"))
    )
    (net (code "56") (name "unconnected-(2POLE-SWITCH-PadNORM)") (class "Default")
      (node (ref "2POLE") (pin "NORM") (pinfunction "SWITCH_NORM") (pintype "passive"))
    )
    (net (code "57") (name "unconnected-(4POLE-SWITCH-PadNORM)") (class "Default")
      (node (ref "4POLE") (pin "NORM") (pinfunction "SWITCH_NORM") (pintype "passive"))
    )
    (net (code "58") (name "unconnected-(IC1A-D-BIAS-Pad2)") (class "Default")
      (node (ref "IC1") (pin "2") (pinfunction "D-BIAS_2") (pintype "bidirectional"))
    )
    (net (code "59") (name "unconnected-(IC1B-D-BIAS-Pad15)") (class "Default")
      (node (ref "IC1") (pin "15") (pinfunction "D-BIAS_15") (pintype "bidirectional"))
    )
    (net (code "60") (name "unconnected-(IC2A-D-BIAS-Pad2)") (class "Default")
      (node (ref "IC2") (pin "2") (pinfunction "D-BIAS_2") (pintype "bidirectional"))
    )
    (net (code "61") (name "unconnected-(IC2B-D-BIAS-Pad15)") (class "Default")
      (node (ref "IC2") (pin "15") (pinfunction "D-BIAS_15") (pintype "bidirectional"))
    )
    (net (code "62") (name "unconnected-(IN1-SWITCH-PadNORM)") (class "Default")
      (node (ref "IN1") (pin "NORM") (pinfunction "SWITCH_NORM") (pintype "passive"))
    )
    (net (code "63") (name "unconnected-(IN2-SWITCH-PadNORM)") (class "Default")
      (node (ref "IN2") (pin "NORM") (pinfunction "SWITCH_NORM") (pintype "passive"))
    )
  )
)
